# Top.net
KiCad netlist of a schematic drawn in EAGLE
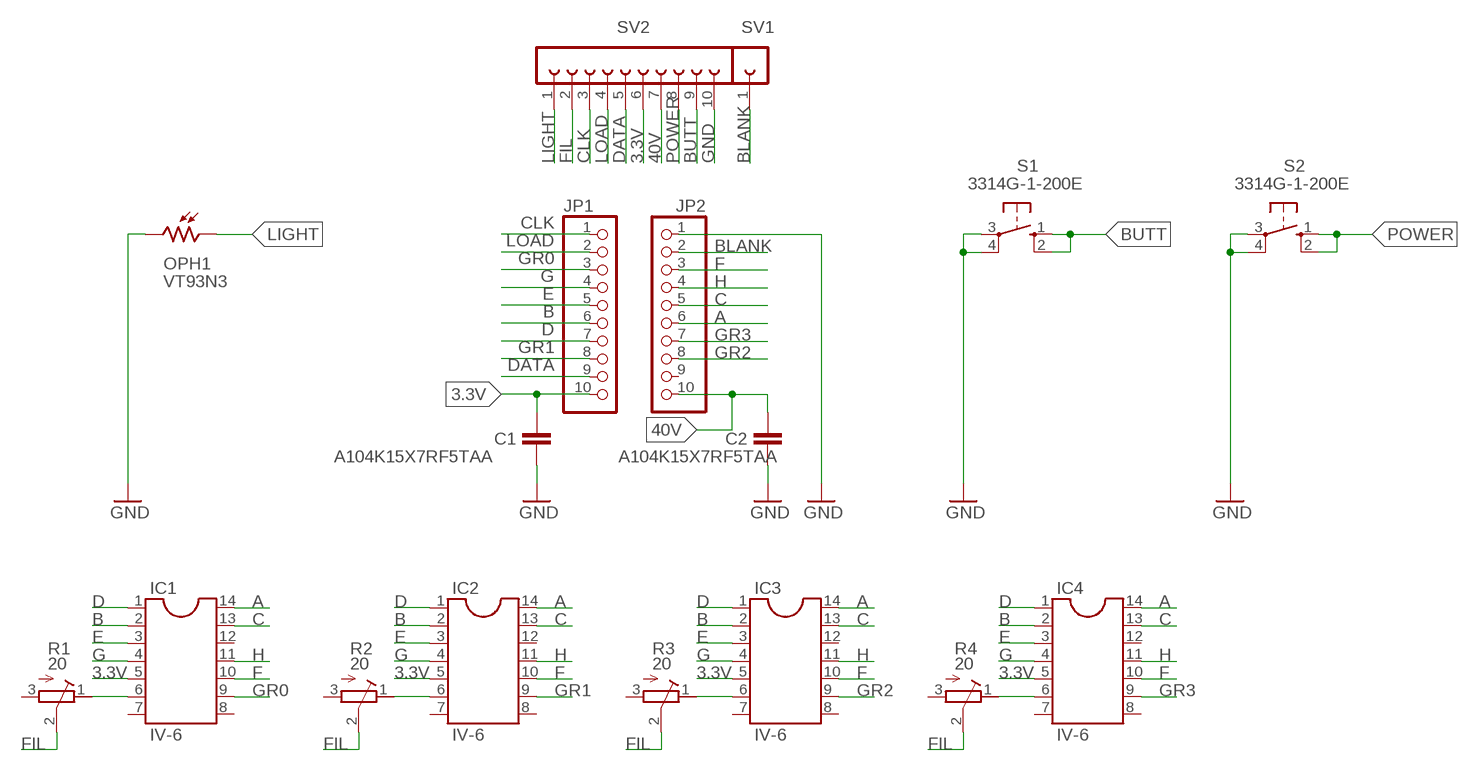
[diagram p0: schematic, sheet 1]

(export (version "E")
  (design (tool "Eeschema 10.0.6"))
  (components
    (comp (ref "C1")
      (value "A104K15X7RF5TAA")
      (footprint "eagle-import:C025-025X050")
      (libsource (lib "eagle-import") (part "A104K15X7RF5TAA"))
    )
    (comp (ref "C2")
      (value "A104K15X7RF5TAA")
      (footprint "eagle-import:C025-025X050")
      (libsource (lib "eagle-import") (part "A104K15X7RF5TAA"))
    )
    (comp (ref "IC1")
      (value "IV-6")
      (footprint "eagle-import:DIL14")
      (libsource (lib "eagle-import") (part "DIL14"))
    )
    (comp (ref "IC2")
      (value "IV-6")
      (footprint "eagle-import:DIL14")
      (libsource (lib "eagle-import") (part "DIL14"))
    )
    (comp (ref "IC3")
      (value "IV-6")
      (footprint "eagle-import:DIL14")
      (libsource (lib "eagle-import") (part "DIL14"))
    )
    (comp (ref "IC4")
      (value "IV-6")
      (footprint "eagle-import:DIL14")
      (libsource (lib "eagle-import") (part "DIL14"))
    )
    (comp (ref "JP1")
      (value "PINHD-1X10")
      (footprint "eagle-import:1X10")
      (libsource (lib "eagle-import") (part "PINHD-1X10"))
    )
    (comp (ref "JP2")
      (value "PINHD-1X10")
      (footprint "eagle-import:1X10")
      (libsource (lib "eagle-import") (part "PINHD-1X10"))
    )
    (comp (ref "OPH1")
      (value "VT93N3")
      (footprint "eagle-import:VT900")
      (libsource (lib "eagle-import") (part "VT93N3"))
    )
    (comp (ref "R1")
      (value "20")
      (footprint "eagle-import:RTRIM3314G")
      (libsource (lib "eagle-import") (part "R-TRIMM3314G"))
    )
    (comp (ref "R2")
      (value "20")
      (footprint "eagle-import:RTRIM3314G")
      (libsource (lib "eagle-import") (part "R-TRIMM3314G"))
    )
    (comp (ref "R3")
      (value "20")
      (footprint "eagle-import:RTRIM3314G")
      (libsource (lib "eagle-import") (part "R-TRIMM3314G"))
    )
    (comp (ref "R4")
      (value "20")
      (footprint "eagle-import:RTRIM3314G")
      (libsource (lib "eagle-import") (part "R-TRIMM3314G"))
    )
    (comp (ref "S1")
      (value "3314G-1-200E")
      (footprint "eagle-import:B3F-10XX")
      (fields (field (name "MPN") "B3F-1000"))
      (libsource (lib "eagle-import") (part "10-XX"))
    )
    (comp (ref "S2")
      (value "3314G-1-200E")
      (footprint "eagle-import:B3F-10XX")
      (fields (field (name "MPN") "B3F-1000"))
      (libsource (lib "eagle-import") (part "10-XX"))
    )
    (comp (ref "SV1")
      (value "FE01")
      (footprint "eagle-import:FE05-1")
      (libsource (lib "eagle-import") (part "FE01"))
    )
    (comp (ref "SV2")
      (value "FE10-1")
      (footprint "eagle-import:FE10")
      (libsource (lib "eagle-import") (part "FE10-1"))
    )
  )
  (nets
    (net (code "1") (name "/A") (class "Default")
      (node (ref "IC1") (pin "14") (pinfunction "14_14") (pintype "passive"))
      (node (ref "IC2") (pin "14") (pinfunction "14_14") (pintype "passive"))
      (node (ref "IC3") (pin "14") (pinfunction "14_14") (pintype "passive"))
      (node (ref "IC4") (pin "14") (pinfunction "14_14") (pintype "passive"))
      (node (ref "JP2") (pin "6") (pinfunction "6_6") (pintype "passive"))
    )
    (net (code "2") (name "/B") (class "Default")
      (node (ref "IC1") (pin "2") (pinfunction "2_2") (pintype "passive"))
      (node (ref "IC2") (pin "2") (pinfunction "2_2") (pintype "passive"))
      (node (ref "IC3") (pin "2") (pinfunction "2_2") (pintype "passive"))
      (node (ref "IC4") (pin "2") (pinfunction "2_2") (pintype "passive"))
      (node (ref "JP1") (pin "6") (pinfunction "6_6") (pintype "passive"))
    )
    (net (code "3") (name "/BLANK") (class "Default")
      (node (ref "JP2") (pin "2") (pinfunction "2_2") (pintype "passive"))
      (node (ref "SV1") (pin "1") (pinfunction "5_1") (pintype "passive"))
    )
    (net (code "4") (name "/C") (class "Default")
      (node (ref "IC1") (pin "13") (pinfunction "13_13") (pintype "passive"))
      (node (ref "IC2") (pin "13") (pinfunction "13_13") (pintype "passive"))
      (node (ref "IC3") (pin "13") (pinfunction "13_13") (pintype "passive"))
      (node (ref "IC4") (pin "13") (pinfunction "13_13") (pintype "passive"))
      (node (ref "JP2") (pin "5") (pinfunction "5_5") (pintype "passive"))
    )
    (net (code "5") (name "/CLK") (class "Default")
      (node (ref "JP1") (pin "1") (pinfunction "1_1") (pintype "passive"))
      (node (ref "SV2") (pin "3") (pinfunction "3_3") (pintype "passive"))
    )
    (net (code "6") (name "/D") (class "Default")
      (node (ref "IC1") (pin "1") (pinfunction "1_1") (pintype "passive"))
      (node (ref "IC2") (pin "1") (pinfunction "1_1") (pintype "passive"))
      (node (ref "IC3") (pin "1") (pinfunction "1_1") (pintype "passive"))
      (node (ref "IC4") (pin "1") (pinfunction "1_1") (pintype "passive"))
      (node (ref "JP1") (pin "7") (pinfunction "7_7") (pintype "passive"))
    )
    (net (code "7") (name "/DATA") (class "Default")
      (node (ref "JP1") (pin "9") (pinfunction "9_9") (pintype "passive"))
      (node (ref "SV2") (pin "5") (pinfunction "5_5") (pintype "passive"))
    )
    (net (code "8") (name "/E") (class "Default")
      (node (ref "IC1") (pin "3") (pinfunction "3_3") (pintype "passive"))
      (node (ref "IC2") (pin "3") (pinfunction "3_3") (pintype "passive"))
      (node (ref "IC3") (pin "3") (pinfunction "3_3") (pintype "passive"))
      (node (ref "IC4") (pin "3") (pinfunction "3_3") (pintype "passive"))
      (node (ref "JP1") (pin "5") (pinfunction "5_5") (pintype "passive"))
    )
    (net (code "9") (name "/F") (class "Default")
      (node (ref "IC1") (pin "10") (pinfunction "10_10") (pintype "passive"))
      (node (ref "IC2") (pin "10") (pinfunction "10_10") (pintype "passive"))
      (node (ref "IC3") (pin "10") (pinfunction "10_10") (pintype "passive"))
      (node (ref "IC4") (pin "10") (pinfunction "10_10") (pintype "passive"))
      (node (ref "JP2") (pin "3") (pinfunction "3_3") (pintype "passive"))
    )
    (net (code "10") (name "/FIL") (class "Default")
      (node (ref "R1") (pin "2") (pinfunction "S_2") (pintype "passive"))
      (node (ref "R2") (pin "2") (pinfunction "S_2") (pintype "passive"))
      (node (ref "R3") (pin "2") (pinfunction "S_2") (pintype "passive"))
      (node (ref "R4") (pin "2") (pinfunction "S_2") (pintype "passive"))
      (node (ref "SV2") (pin "2") (pinfunction "2_2") (pintype "passive"))
    )
    (net (code "11") (name "/G") (class "Default")
      (node (ref "IC1") (pin "4") (pinfunction "4_4") (pintype "passive"))
      (node (ref "IC2") (pin "4") (pinfunction "4_4") (pintype "passive"))
      (node (ref "IC3") (pin "4") (pinfunction "4_4") (pintype "passive"))
      (node (ref "IC4") (pin "4") (pinfunction "4_4") (pintype "passive"))
      (node (ref "JP1") (pin "4") (pinfunction "4_4") (pintype "passive"))
    )
    (net (code "12") (name "/GR0") (class "Default")
      (node (ref "IC1") (pin "9") (pinfunction "9_9") (pintype "passive"))
      (node (ref "JP1") (pin "3") (pinfunction "3_3") (pintype "passive"))
    )
    (net (code "13") (name "/GR1") (class "Default")
      (node (ref "IC2") (pin "9") (pinfunction "9_9") (pintype "passive"))
      (node (ref "JP1") (pin "8") (pinfunction "8_8") (pintype "passive"))
    )
    (net (code "14") (name "/GR2") (class "Default")
      (node (ref "IC3") (pin "9") (pinfunction "9_9") (pintype "passive"))
      (node (ref "JP2") (pin "8") (pinfunction "8_8") (pintype "passive"))
    )
    (net (code "15") (name "/GR3") (class "Default")
      (node (ref "IC4") (pin "9") (pinfunction "9_9") (pintype "passive"))
      (node (ref "JP2") (pin "7") (pinfunction "7_7") (pintype "passive"))
    )
    (net (code "16") (name "/H") (class "Default")
      (node (ref "IC1") (pin "11") (pinfunction "11_11") (pintype "passive"))
      (node (ref "IC2") (pin "11") (pinfunction "11_11") (pintype "passive"))
      (node (ref "IC3") (pin "11") (pinfunction "11_11") (pintype "passive"))
      (node (ref "IC4") (pin "11") (pinfunction "11_11") (pintype "passive"))
      (node (ref "JP2") (pin "4") (pinfunction "4_4") (pintype "passive"))
    )
    (net (code "17") (name "/LOAD") (class "Default")
      (node (ref "JP1") (pin "2") (pinfunction "2_2") (pintype "passive"))
      (node (ref "SV2") (pin "4") (pinfunction "4_4") (pintype "passive"))
    )
    (net (code "18") (name "3.3V") (class "Default")
      (node (ref "C1") (pin "1") (pinfunction "1_1") (pintype "passive"))
      (node (ref "IC1") (pin "5") (pinfunction "5_5") (pintype "passive"))
      (node (ref "IC2") (pin "5") (pinfunction "5_5") (pintype "passive"))
      (node (ref "IC3") (pin "5") (pinfunction "5_5") (pintype "passive"))
      (node (ref "IC4") (pin "5") (pinfunction "5_5") (pintype "passive"))
      (node (ref "JP1") (pin "10") (pinfunction "10_10") (pintype "passive"))
      (node (ref "SV2") (pin "6") (pinfunction "6_6") (pintype "passive"))
    )
    (net (code "19") (name "40V") (class "Default")
      (node (ref "C2") (pin "1") (pinfunction "1_1") (pintype "passive"))
      (node (ref "JP2") (pin "10") (pinfunction "10_10") (pintype "passive"))
      (node (ref "SV2") (pin "7") (pinfunction "7_7") (pintype "passive"))
    )
    (net (code "20") (name "BUTT") (class "Default")
      (node (ref "S1") (pin "1") (pinfunction "S_1") (pintype "passive"))
      (node (ref "S1") (pin "2") (pinfunction "S1_2") (pintype "passive"))
      (node (ref "SV2") (pin "9") (pinfunction "9_9") (pintype "passive"))
    )
    (net (code "21") (name "GND") (class "Default")
      (node (ref "C1") (pin "2") (pinfunction "2_2") (pintype "passive"))
      (node (ref "C2") (pin "2") (pinfunction "2_2") (pintype "passive"))
      (node (ref "JP2") (pin "1") (pinfunction "1_1") (pintype "passive"))
      (node (ref "OPH1") (pin "2") (pinfunction "2_2") (pintype "passive"))
      (node (ref "S1") (pin "3") (pinfunction "P_3") (pintype "passive"))
      (node (ref "S1") (pin "4") (pinfunction "P1_4") (pintype "passive"))
      (node (ref "S2") (pin "3") (pinfunction "P_3") (pintype "passive"))
      (node (ref "S2") (pin "4") (pinfunction "P1_4") (pintype "passive"))
      (node (ref "SV2") (pin "10") (pinfunction "10_10") (pintype "passive"))
    )
    (net (code "22") (name "LIGHT") (class "Default")
      (node (ref "OPH1") (pin "1") (pinfunction "1_1") (pintype "passive"))
      (node (ref "SV2") (pin "1") (pinfunction "1_1") (pintype "passive"))
    )
    (net (code "23") (name "Net-(R1-E)") (class "Default")
      (node (ref "IC1") (pin "6") (pinfunction "6_6") (pintype "passive"))
      (node (ref "R1") (pin "1") (pinfunction "E_1") (pintype "passive"))
    )
    (net (code "24") (name "Net-(R2-E)") (class "Default")
      (node (ref "IC2") (pin "6") (pinfunction "6_6") (pintype "passive"))
      (node (ref "R2") (pin "1") (pinfunction "E_1") (pintype "passive"))
    )
    (net (code "25") (name "Net-(R3-E)") (class "Default")
      (node (ref "IC3") (pin "6") (pinfunction "6_6") (pintype "passive"))
      (node (ref "R3") (pin "1") (pinfunction "E_1") (pintype "passive"))
    )
    (net (code "26") (name "Net-(R4-E)") (class "Default")
      (node (ref "IC4") (pin "6") (pinfunction "6_6") (pintype "passive"))
      (node (ref "R4") (pin "1") (pinfunction "E_1") (pintype "passive"))
    )
    (net (code "27") (name "POWER") (class "Default")
      (node (ref "S2") (pin "1") (pinfunction "S_1") (pintype "passive"))
      (node (ref "S2") (pin "2") (pinfunction "S1_2") (pintype "passive"))
      (node (ref "SV2") (pin "8") (pinfunction "8_8") (pintype "passive"))
    )
    (net (code "28") (name "unconnected-(IC1-Pad7)") (class "Default")
      (node (ref "IC1") (pin "7") (pinfunction "7_7") (pintype "passive"))
    )
    (net (code "29") (name "unconnected-(IC1-Pad8)") (class "Default")
      (node (ref "IC1") (pin "8") (pinfunction "8_8") (pintype "passive"))
    )
    (net (code "30") (name "unconnected-(IC1-Pad12)") (class "Default")
      (node (ref "IC1") (pin "12") (pinfunction "12_12") (pintype "passive"))
    )
    (net (code "31") (name "unconnected-(IC2-Pad7)") (class "Default")
      (node (ref "IC2") (pin "7") (pinfunction "7_7") (pintype "passive"))
    )
    (net (code "32") (name "unconnected-(IC2-Pad8)") (class "Default")
      (node (ref "IC2") (pin "8") (pinfunction "8_8") (pintype "passive"))
    )
    (net (code "33") (name "unconnected-(IC2-Pad12)") (class "Default")
      (node (ref "IC2") (pin "12") (pinfunction "12_12") (pintype "passive"))
    )
    (net (code "34") (name "unconnected-(IC3-Pad7)") (class "Default")
      (node (ref "IC3") (pin "7") (pinfunction "7_7") (pintype "passive"))
    )
    (net (code "35") (name "unconnected-(IC3-Pad8)") (class "Default")
      (node (ref "IC3") (pin "8") (pinfunction "8_8") (pintype "passive"))
    )
    (net (code "36") (name "unconnected-(IC3-Pad12)") (class "Default")
      (node (ref "IC3") (pin "12") (pinfunction "12_12") (pintype "passive"))
    )
    (net (code "37") (name "unconnected-(IC4-Pad7)") (class "Default")
      (node (ref "IC4") (pin "7") (pinfunction "7_7") (pintype "passive"))
    )
    (net (code "38") (name "unconnected-(IC4-Pad8)") (class "Default")
      (node (ref "IC4") (pin "8") (pinfunction "8_8") (pintype "passive"))
    )
    (net (code "39") (name "unconnected-(IC4-Pad12)") (class "Default")
      (node (ref "IC4") (pin "12") (pinfunction "12_12") (pintype "passive"))
    )
    (net (code "40") (name "unconnected-(JP2-Pad9)") (class "Default")
      (node (ref "JP2") (pin "9") (pinfunction "9_9") (pintype "passive"))
    )
    (net (code "41") (name "unconnected-(R1-A-Pad3)") (class "Default")
      (node (ref "R1") (pin "3") (pinfunction "A_3") (pintype "passive"))
    )
    (net (code "42") (name "unconnected-(R2-A-Pad3)") (class "Default")
      (node (ref "R2") (pin "3") (pinfunction "A_3") (pintype "passive"))
    )
    (net (code "43") (name "unconnected-(R3-A-Pad3)") (class "Default")
      (node (ref "R3") (pin "3") (pinfunction "A_3") (pintype "passive"))
    )
    (net (code "44") (name "unconnected-(R4-A-Pad3)") (class "Default")
      (node (ref "R4") (pin "3") (pinfunction "A_3") (pintype "passive"))
    )
  )
)
